# OPEN_DROP_DIGISCOPE_BOARD_1.net
KiCad netlist of a schematic drawn in EAGLE
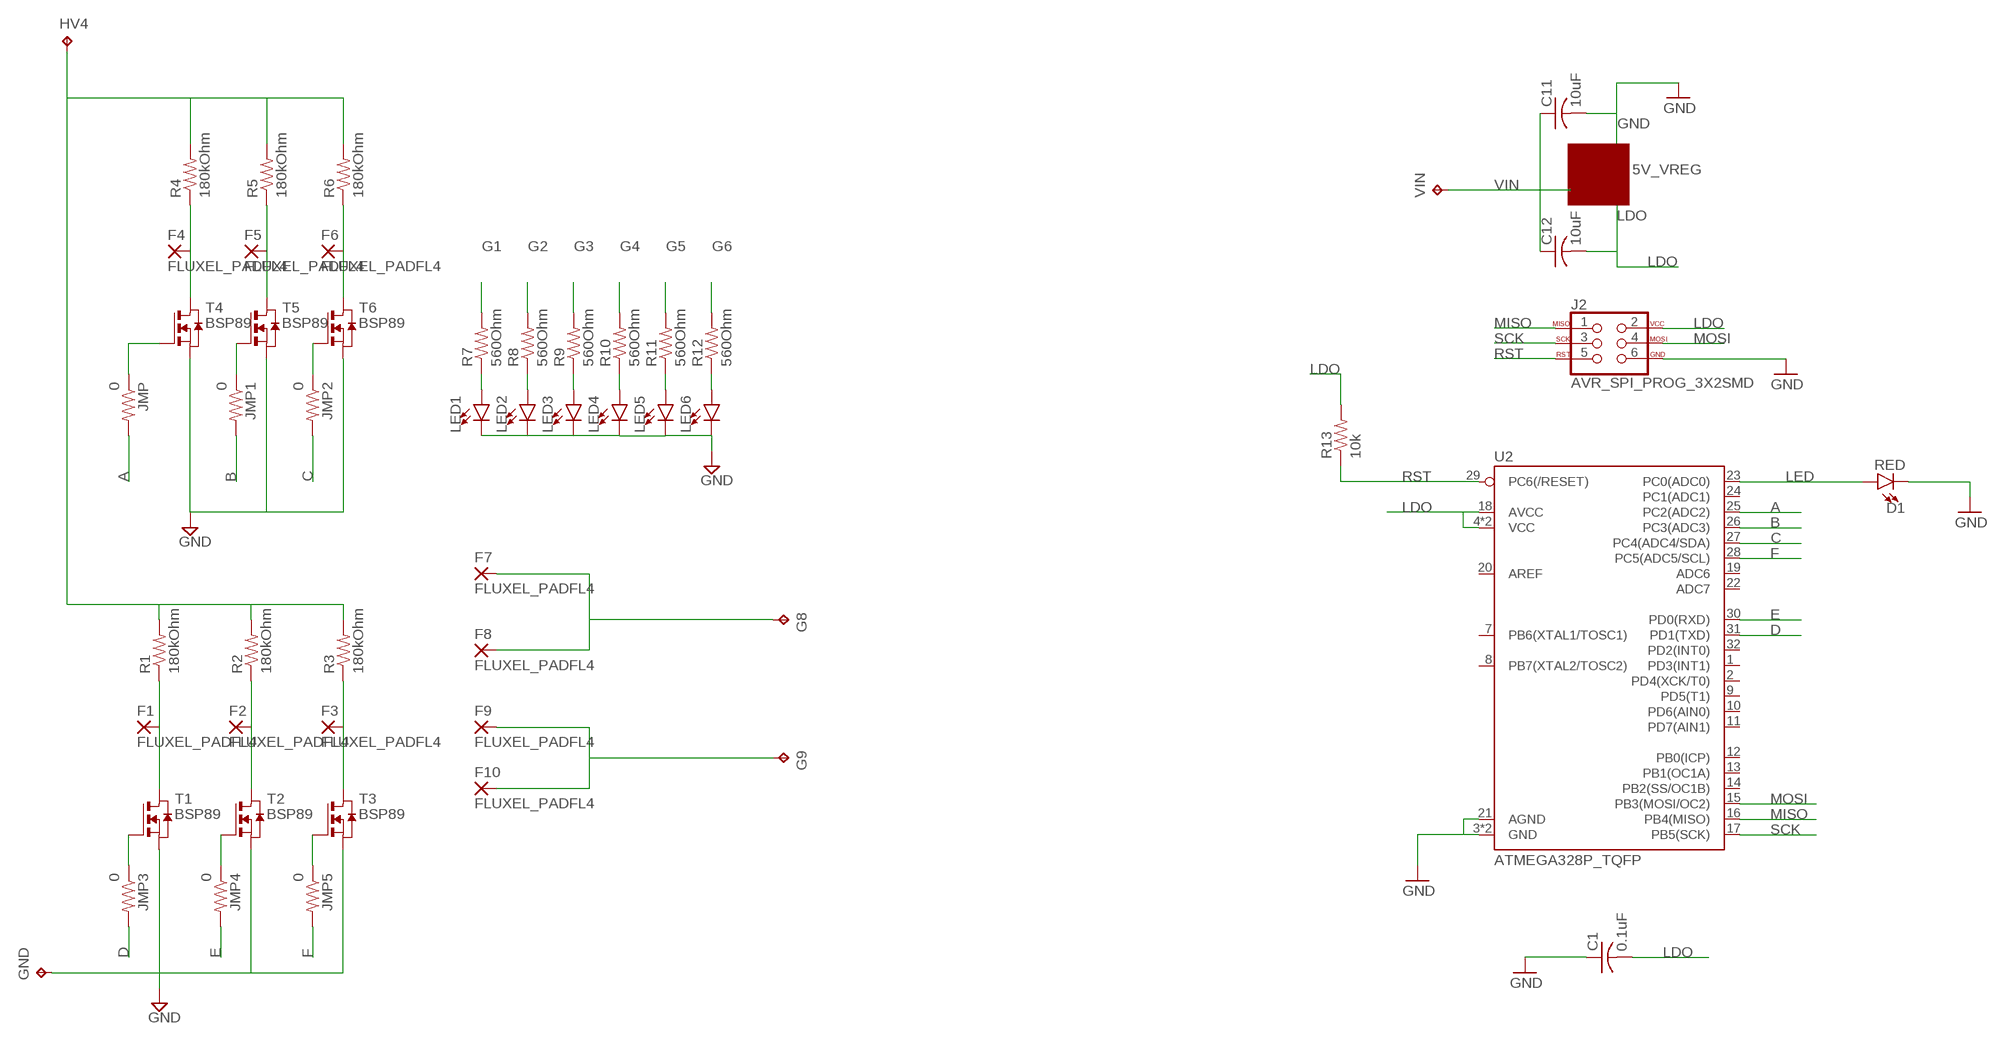
[diagram p0: schematic, sheet 1]

(export (version "E")
  (design (tool "Eeschema 10.0.6"))
  (components
    (comp (ref "5V_VREG")
      (value "MOSFET_PCH-DMG2305UX-7")
      (footprint "eagle-import:SOT23-3")
      (libsource (lib "eagle-import") (part "MOSFET_PCH-DMG2305UX-7"))
    )
    (comp (ref "C1")
      (value "0.1uF")
      (footprint "eagle-import:C1206")
      (libsource (lib "eagle-import") (part "C-USC1206"))
    )
    (comp (ref "C11")
      (value "10uF")
      (footprint "eagle-import:C1206")
      (libsource (lib "eagle-import") (part "C-USC1206"))
    )
    (comp (ref "C12")
      (value "10uF")
      (footprint "eagle-import:C1206")
      (libsource (lib "eagle-import") (part "C-USC1206"))
    )
    (comp (ref "D1")
      (value "RED")
      (footprint "eagle-import:LED-1206")
      (libsource (lib "eagle-import") (part "LED-RED1206"))
    )
    (comp (ref "F1")
      (value "FLUXEL_PADFL4")
      (footprint "eagle-import:FLUXEL_PAD4")
      (libsource (lib "eagle-import") (part "FLUXEL_PADFL4"))
    )
    (comp (ref "F2")
      (value "FLUXEL_PADFL4")
      (footprint "eagle-import:FLUXEL_PAD4")
      (libsource (lib "eagle-import") (part "FLUXEL_PADFL4"))
    )
    (comp (ref "F3")
      (value "FLUXEL_PADFL4")
      (footprint "eagle-import:FLUXEL_PAD4")
      (libsource (lib "eagle-import") (part "FLUXEL_PADFL4"))
    )
    (comp (ref "F4")
      (value "FLUXEL_PADFL4")
      (footprint "eagle-import:FLUXEL_PAD4")
      (libsource (lib "eagle-import") (part "FLUXEL_PADFL4"))
    )
    (comp (ref "F5")
      (value "FLUXEL_PADFL4")
      (footprint "eagle-import:FLUXEL_PAD4")
      (libsource (lib "eagle-import") (part "FLUXEL_PADFL4"))
    )
    (comp (ref "F6")
      (value "FLUXEL_PADFL4")
      (footprint "eagle-import:FLUXEL_PAD4")
      (libsource (lib "eagle-import") (part "FLUXEL_PADFL4"))
    )
    (comp (ref "F7")
      (value "FLUXEL_PADFL4")
      (footprint "eagle-import:FLUXEL_PAD4")
      (libsource (lib "eagle-import") (part "FLUXEL_PADFL4"))
    )
    (comp (ref "F8")
      (value "FLUXEL_PADFL4")
      (footprint "eagle-import:FLUXEL_PAD4")
      (libsource (lib "eagle-import") (part "FLUXEL_PADFL4"))
    )
    (comp (ref "F9")
      (value "FLUXEL_PADFL4")
      (footprint "eagle-import:FLUXEL_PAD4")
      (libsource (lib "eagle-import") (part "FLUXEL_PADFL4"))
    )
    (comp (ref "F10")
      (value "FLUXEL_PADFL4")
      (footprint "eagle-import:FLUXEL_PAD4")
      (libsource (lib "eagle-import") (part "FLUXEL_PADFL4"))
    )
    (comp (ref "G8")
      (value "TPB2,54")
      (footprint "eagle-import:B2,54")
      (libsource (lib "eagle-import") (part "TPB2,54"))
    )
    (comp (ref "G9")
      (value "TPB2,54")
      (footprint "eagle-import:B2,54")
      (libsource (lib "eagle-import") (part "TPB2,54"))
    )
    (comp (ref "GND")
      (value "TPB2,54")
      (footprint "eagle-import:B2,54")
      (libsource (lib "eagle-import") (part "TPB2,54"))
    )
    (comp (ref "HV4")
      (value "TPB2,54")
      (footprint "eagle-import:B2,54")
      (libsource (lib "eagle-import") (part "TPB2,54"))
    )
    (comp (ref "J2")
      (value "AVR_SPI_PROG_3X2SMD")
      (footprint "eagle-import:2X3_SMT_POSTS")
      (libsource (lib "eagle-import") (part "AVR_SPI_PROG_3X2SMD"))
    )
    (comp (ref "JMP")
      (value "0")
      (footprint "eagle-import:M1206")
      (libsource (lib "eagle-import") (part "R-US_M1206"))
    )
    (comp (ref "JMP1")
      (value "0")
      (footprint "eagle-import:M1206")
      (libsource (lib "eagle-import") (part "R-US_M1206"))
    )
    (comp (ref "JMP2")
      (value "0")
      (footprint "eagle-import:M1206")
      (libsource (lib "eagle-import") (part "R-US_M1206"))
    )
    (comp (ref "JMP3")
      (value "0")
      (footprint "eagle-import:M1206")
      (libsource (lib "eagle-import") (part "R-US_M1206"))
    )
    (comp (ref "JMP4")
      (value "0")
      (footprint "eagle-import:M1206")
      (libsource (lib "eagle-import") (part "R-US_M1206"))
    )
    (comp (ref "JMP5")
      (value "0")
      (footprint "eagle-import:M1206")
      (libsource (lib "eagle-import") (part "R-US_M1206"))
    )
    (comp (ref "LED1")
      (value "LED1206")
      (footprint "eagle-import:LED-1206")
      (libsource (lib "eagle-import") (part "LED1206"))
    )
    (comp (ref "LED2")
      (value "LED1206")
      (footprint "eagle-import:LED-1206")
      (libsource (lib "eagle-import") (part "LED1206"))
    )
    (comp (ref "LED3")
      (value "LED1206")
      (footprint "eagle-import:LED-1206")
      (libsource (lib "eagle-import") (part "LED1206"))
    )
    (comp (ref "LED4")
      (value "LED1206")
      (footprint "eagle-import:LED-1206")
      (libsource (lib "eagle-import") (part "LED1206"))
    )
    (comp (ref "LED5")
      (value "LED1206")
      (footprint "eagle-import:LED-1206")
      (libsource (lib "eagle-import") (part "LED1206"))
    )
    (comp (ref "LED6")
      (value "LED1206")
      (footprint "eagle-import:LED-1206")
      (libsource (lib "eagle-import") (part "LED1206"))
    )
    (comp (ref "R1")
      (value "180kOhm")
      (footprint "eagle-import:M1206")
      (libsource (lib "eagle-import") (part "R-US_M1206"))
    )
    (comp (ref "R2")
      (value "180kOhm")
      (footprint "eagle-import:M1206")
      (libsource (lib "eagle-import") (part "R-US_M1206"))
    )
    (comp (ref "R3")
      (value "180kOhm")
      (footprint "eagle-import:M1206")
      (libsource (lib "eagle-import") (part "R-US_M1206"))
    )
    (comp (ref "R4")
      (value "180kOhm")
      (footprint "eagle-import:M1206")
      (libsource (lib "eagle-import") (part "R-US_M1206"))
    )
    (comp (ref "R5")
      (value "180kOhm")
      (footprint "eagle-import:M1206")
      (libsource (lib "eagle-import") (part "R-US_M1206"))
    )
    (comp (ref "R6")
      (value "180kOhm")
      (footprint "eagle-import:M1206")
      (libsource (lib "eagle-import") (part "R-US_M1206"))
    )
    (comp (ref "R7")
      (value "560Ohm")
      (footprint "eagle-import:M1206")
      (libsource (lib "eagle-import") (part "R-US_M1206"))
    )
    (comp (ref "R8")
      (value "560Ohm")
      (footprint "eagle-import:M1206")
      (libsource (lib "eagle-import") (part "R-US_M1206"))
    )
    (comp (ref "R9")
      (value "560Ohm")
      (footprint "eagle-import:M1206")
      (libsource (lib "eagle-import") (part "R-US_M1206"))
    )
    (comp (ref "R10")
      (value "560Ohm")
      (footprint "eagle-import:M1206")
      (libsource (lib "eagle-import") (part "R-US_M1206"))
    )
    (comp (ref "R11")
      (value "560Ohm")
      (footprint "eagle-import:M1206")
      (libsource (lib "eagle-import") (part "R-US_M1206"))
    )
    (comp (ref "R12")
      (value "560Ohm")
      (footprint "eagle-import:M1206")
      (libsource (lib "eagle-import") (part "R-US_M1206"))
    )
    (comp (ref "R13")
      (value "10k")
      (footprint "eagle-import:R1206")
      (libsource (lib "eagle-import") (part "R-US_R1206"))
    )
    (comp (ref "T1")
      (value "BSP89")
      (footprint "eagle-import:SOT223")
      (libsource (lib "eagle-import") (part "NMOSSOT223"))
    )
    (comp (ref "T2")
      (value "BSP89")
      (footprint "eagle-import:SOT223")
      (libsource (lib "eagle-import") (part "NMOSSOT223"))
    )
    (comp (ref "T3")
      (value "BSP89")
      (footprint "eagle-import:SOT223")
      (libsource (lib "eagle-import") (part "NMOSSOT223"))
    )
    (comp (ref "T4")
      (value "BSP89")
      (footprint "eagle-import:SOT223")
      (libsource (lib "eagle-import") (part "NMOSSOT223"))
    )
    (comp (ref "T5")
      (value "BSP89")
      (footprint "eagle-import:SOT223")
      (libsource (lib "eagle-import") (part "NMOSSOT223"))
    )
    (comp (ref "T6")
      (value "BSP89")
      (footprint "eagle-import:SOT223")
      (libsource (lib "eagle-import") (part "NMOSSOT223"))
    )
    (comp (ref "U2")
      (value "ATMEGA328P_TQFP")
      (footprint "eagle-import:TQFP32-08")
      (libsource (lib "eagle-import") (part "ATMEGA328P_TQFP"))
    )
    (comp (ref "VIN")
      (value "TPB2,54")
      (footprint "eagle-import:B2,54")
      (libsource (lib "eagle-import") (part "TPB2,54"))
    )
  )
  (nets
    (net (code "1") (name "/A") (class "Default")
      (node (ref "JMP") (pin "2") (pinfunction "2_2") (pintype "passive"))
      (node (ref "U2") (pin "25") (pinfunction "PC2(ADC2)_25") (pintype "bidirectional"))
    )
    (net (code "2") (name "/B") (class "Default")
      (node (ref "JMP1") (pin "2") (pinfunction "2_2") (pintype "passive"))
      (node (ref "U2") (pin "26") (pinfunction "PC3(ADC3)_26") (pintype "bidirectional"))
    )
    (net (code "3") (name "/C") (class "Default")
      (node (ref "JMP2") (pin "2") (pinfunction "2_2") (pintype "passive"))
      (node (ref "U2") (pin "27") (pinfunction "PC4(ADC4/SDA)_27") (pintype "bidirectional"))
    )
    (net (code "4") (name "/D") (class "Default")
      (node (ref "JMP3") (pin "2") (pinfunction "2_2") (pintype "passive"))
      (node (ref "U2") (pin "31") (pinfunction "PD1(TXD)_31") (pintype "bidirectional"))
    )
    (net (code "5") (name "/E") (class "Default")
      (node (ref "JMP4") (pin "2") (pinfunction "2_2") (pintype "passive"))
      (node (ref "U2") (pin "30") (pinfunction "PD0(RXD)_30") (pintype "bidirectional"))
    )
    (net (code "6") (name "/F") (class "Default")
      (node (ref "JMP5") (pin "2") (pinfunction "2_2") (pintype "passive"))
      (node (ref "U2") (pin "28") (pinfunction "PC5(ADC5/SCL)_28") (pintype "bidirectional"))
    )
    (net (code "7") (name "/G1") (class "Default")
      (node (ref "JMP3") (pin "1") (pinfunction "1_1") (pintype "passive"))
      (node (ref "R7") (pin "2") (pinfunction "2_2") (pintype "passive"))
      (node (ref "T1") (pin "1") (pinfunction "G_1") (pintype "passive"))
    )
    (net (code "8") (name "/G2") (class "Default")
      (node (ref "JMP4") (pin "1") (pinfunction "1_1") (pintype "passive"))
      (node (ref "R8") (pin "2") (pinfunction "2_2") (pintype "passive"))
      (node (ref "T2") (pin "1") (pinfunction "G_1") (pintype "passive"))
    )
    (net (code "9") (name "/G3") (class "Default")
      (node (ref "JMP5") (pin "1") (pinfunction "1_1") (pintype "passive"))
      (node (ref "R9") (pin "2") (pinfunction "2_2") (pintype "passive"))
      (node (ref "T3") (pin "1") (pinfunction "G_1") (pintype "passive"))
    )
    (net (code "10") (name "/G4") (class "Default")
      (node (ref "JMP") (pin "1") (pinfunction "1_1") (pintype "passive"))
      (node (ref "R10") (pin "2") (pinfunction "2_2") (pintype "passive"))
      (node (ref "T4") (pin "1") (pinfunction "G_1") (pintype "passive"))
    )
    (net (code "11") (name "/G5") (class "Default")
      (node (ref "JMP1") (pin "1") (pinfunction "1_1") (pintype "passive"))
      (node (ref "R11") (pin "2") (pinfunction "2_2") (pintype "passive"))
      (node (ref "T5") (pin "1") (pinfunction "G_1") (pintype "passive"))
    )
    (net (code "12") (name "/G6") (class "Default")
      (node (ref "JMP2") (pin "1") (pinfunction "1_1") (pintype "passive"))
      (node (ref "R12") (pin "2") (pinfunction "2_2") (pintype "passive"))
      (node (ref "T6") (pin "1") (pinfunction "G_1") (pintype "passive"))
    )
    (net (code "13") (name "/LDO") (class "Default")
      (node (ref "5V_VREG") (pin "2") (pinfunction "S_2") (pintype "bidirectional"))
      (node (ref "C1") (pin "2") (pinfunction "2_2") (pintype "passive"))
      (node (ref "C12") (pin "2") (pinfunction "2_2") (pintype "passive"))
      (node (ref "J2") (pin "2") (pinfunction "2_2") (pintype "passive"))
      (node (ref "R13") (pin "2") (pinfunction "2_2") (pintype "passive"))
      (node (ref "U2") (pin "18") (pinfunction "AVCC_18") (pintype "bidirectional"))
      (node (ref "U2") (pin "4") (pinfunction "VCC_4") (pintype "bidirectional"))
      (node (ref "U2") (pin "6") (pinfunction "VCC_6") (pintype "bidirectional"))
    )
    (net (code "14") (name "/LED") (class "Default")
      (node (ref "D1") (pin "A") (pinfunction "A_A") (pintype "passive"))
      (node (ref "U2") (pin "23") (pinfunction "PC0(ADC0)_23") (pintype "bidirectional"))
    )
    (net (code "15") (name "/MISO") (class "Default")
      (node (ref "J2") (pin "1") (pinfunction "1_1") (pintype "passive"))
      (node (ref "U2") (pin "16") (pinfunction "PB4(MISO)_16") (pintype "bidirectional"))
    )
    (net (code "16") (name "/MOSI") (class "Default")
      (node (ref "J2") (pin "4") (pinfunction "4_4") (pintype "passive"))
      (node (ref "U2") (pin "15") (pinfunction "PB3(MOSI/OC2)_15") (pintype "bidirectional"))
    )
    (net (code "17") (name "/RST") (class "Default")
      (node (ref "J2") (pin "5") (pinfunction "5_5") (pintype "passive"))
      (node (ref "R13") (pin "1") (pinfunction "1_1") (pintype "passive"))
      (node (ref "U2") (pin "29") (pinfunction "PC6(/RESET)_29") (pintype "bidirectional"))
    )
    (net (code "18") (name "/SCK") (class "Default")
      (node (ref "J2") (pin "3") (pinfunction "3_3") (pintype "passive"))
      (node (ref "U2") (pin "17") (pinfunction "PB5(SCK)_17") (pintype "bidirectional"))
    )
    (net (code "19") (name "/VIN") (class "Default")
      (node (ref "5V_VREG") (pin "1") (pinfunction "G_1") (pintype "bidirectional"))
      (node (ref "C11") (pin "1") (pinfunction "1_1") (pintype "passive"))
      (node (ref "C12") (pin "1") (pinfunction "1_1") (pintype "passive"))
      (node (ref "VIN") (pin "TP") (pinfunction "TP_TP") (pintype "input"))
    )
    (net (code "20") (name "GND") (class "Default")
      (node (ref "5V_VREG") (pin "3") (pinfunction "D_3") (pintype "bidirectional"))
      (node (ref "C1") (pin "1") (pinfunction "1_1") (pintype "passive"))
      (node (ref "C11") (pin "2") (pinfunction "2_2") (pintype "passive"))
      (node (ref "D1") (pin "C") (pinfunction "C_C") (pintype "passive"))
      (node (ref "GND") (pin "TP") (pinfunction "TP_TP") (pintype "input"))
      (node (ref "J2") (pin "6") (pinfunction "6_6") (pintype "passive"))
      (node (ref "LED1") (pin "C") (pinfunction "C_C") (pintype "passive"))
      (node (ref "LED2") (pin "C") (pinfunction "C_C") (pintype "passive"))
      (node (ref "LED3") (pin "C") (pinfunction "C_C") (pintype "passive"))
      (node (ref "LED4") (pin "C") (pinfunction "C_C") (pintype "passive"))
      (node (ref "LED5") (pin "C") (pinfunction "C_C") (pintype "passive"))
      (node (ref "LED6") (pin "C") (pinfunction "C_C") (pintype "passive"))
      (node (ref "T1") (pin "3") (pinfunction "S_3") (pintype "passive"))
      (node (ref "T2") (pin "3") (pinfunction "S_3") (pintype "passive"))
      (node (ref "T3") (pin "3") (pinfunction "S_3") (pintype "passive"))
      (node (ref "T4") (pin "3") (pinfunction "S_3") (pintype "passive"))
      (node (ref "T5") (pin "3") (pinfunction "S_3") (pintype "passive"))
      (node (ref "T6") (pin "3") (pinfunction "S_3") (pintype "passive"))
      (node (ref "U2") (pin "21") (pinfunction "AGND_21") (pintype "bidirectional"))
      (node (ref "U2") (pin "3") (pinfunction "GND_3") (pintype "bidirectional"))
      (node (ref "U2") (pin "5") (pinfunction "GND_5") (pintype "bidirectional"))
    )
    (net (code "21") (name "Net-(F1-P)") (class "Default")
      (node (ref "F1") (pin "1") (pinfunction "P_1") (pintype "passive"))
      (node (ref "R1") (pin "1") (pinfunction "1_1") (pintype "passive"))
      (node (ref "T1") (pin "2") (pinfunction "D_2") (pintype "passive"))
      (node (ref "T1") (pin "4") (pinfunction "D_4") (pintype "passive"))
    )
    (net (code "22") (name "Net-(F2-P)") (class "Default")
      (node (ref "F2") (pin "1") (pinfunction "P_1") (pintype "passive"))
      (node (ref "R2") (pin "1") (pinfunction "1_1") (pintype "passive"))
      (node (ref "T2") (pin "2") (pinfunction "D_2") (pintype "passive"))
      (node (ref "T2") (pin "4") (pinfunction "D_4") (pintype "passive"))
    )
    (net (code "23") (name "Net-(F3-P)") (class "Default")
      (node (ref "F3") (pin "1") (pinfunction "P_1") (pintype "passive"))
      (node (ref "R3") (pin "1") (pinfunction "1_1") (pintype "passive"))
      (node (ref "T3") (pin "2") (pinfunction "D_2") (pintype "passive"))
      (node (ref "T3") (pin "4") (pinfunction "D_4") (pintype "passive"))
    )
    (net (code "24") (name "Net-(F4-P)") (class "Default")
      (node (ref "F4") (pin "1") (pinfunction "P_1") (pintype "passive"))
      (node (ref "R4") (pin "1") (pinfunction "1_1") (pintype "passive"))
      (node (ref "T4") (pin "2") (pinfunction "D_2") (pintype "passive"))
      (node (ref "T4") (pin "4") (pinfunction "D_4") (pintype "passive"))
    )
    (net (code "25") (name "Net-(F5-P)") (class "Default")
      (node (ref "F5") (pin "1") (pinfunction "P_1") (pintype "passive"))
      (node (ref "R5") (pin "1") (pinfunction "1_1") (pintype "passive"))
      (node (ref "T5") (pin "2") (pinfunction "D_2") (pintype "passive"))
      (node (ref "T5") (pin "4") (pinfunction "D_4") (pintype "passive"))
    )
    (net (code "26") (name "Net-(F6-P)") (class "Default")
      (node (ref "F6") (pin "1") (pinfunction "P_1") (pintype "passive"))
      (node (ref "R6") (pin "1") (pinfunction "1_1") (pintype "passive"))
      (node (ref "T6") (pin "2") (pinfunction "D_2") (pintype "passive"))
      (node (ref "T6") (pin "4") (pinfunction "D_4") (pintype "passive"))
    )
    (net (code "27") (name "Net-(F7-P)") (class "Default")
      (node (ref "F7") (pin "1") (pinfunction "P_1") (pintype "passive"))
      (node (ref "F8") (pin "1") (pinfunction "P_1") (pintype "passive"))
      (node (ref "G8") (pin "TP") (pinfunction "TP_TP") (pintype "input"))
    )
    (net (code "28") (name "Net-(F10-P)") (class "Default")
      (node (ref "F10") (pin "1") (pinfunction "P_1") (pintype "passive"))
      (node (ref "F9") (pin "1") (pinfunction "P_1") (pintype "passive"))
      (node (ref "G9") (pin "TP") (pinfunction "TP_TP") (pintype "input"))
    )
    (net (code "29") (name "Net-(HV4-PadTP)") (class "Default")
      (node (ref "HV4") (pin "TP") (pinfunction "TP_TP") (pintype "input"))
      (node (ref "R1") (pin "2") (pinfunction "2_2") (pintype "passive"))
      (node (ref "R2") (pin "2") (pinfunction "2_2") (pintype "passive"))
      (node (ref "R3") (pin "2") (pinfunction "2_2") (pintype "passive"))
      (node (ref "R4") (pin "2") (pinfunction "2_2") (pintype "passive"))
      (node (ref "R5") (pin "2") (pinfunction "2_2") (pintype "passive"))
      (node (ref "R6") (pin "2") (pinfunction "2_2") (pintype "passive"))
    )
    (net (code "30") (name "Net-(LED1-PadA)") (class "Default")
      (node (ref "LED1") (pin "A") (pinfunction "A_A") (pintype "passive"))
      (node (ref "R7") (pin "1") (pinfunction "1_1") (pintype "passive"))
    )
    (net (code "31") (name "Net-(LED2-PadA)") (class "Default")
      (node (ref "LED2") (pin "A") (pinfunction "A_A") (pintype "passive"))
      (node (ref "R8") (pin "1") (pinfunction "1_1") (pintype "passive"))
    )
    (net (code "32") (name "Net-(LED3-PadA)") (class "Default")
      (node (ref "LED3") (pin "A") (pinfunction "A_A") (pintype "passive"))
      (node (ref "R9") (pin "1") (pinfunction "1_1") (pintype "passive"))
    )
    (net (code "33") (name "Net-(LED4-PadA)") (class "Default")
      (node (ref "LED4") (pin "A") (pinfunction "A_A") (pintype "passive"))
      (node (ref "R10") (pin "1") (pinfunction "1_1") (pintype "passive"))
    )
    (net (code "34") (name "Net-(LED5-PadA)") (class "Default")
      (node (ref "LED5") (pin "A") (pinfunction "A_A") (pintype "passive"))
      (node (ref "R11") (pin "1") (pinfunction "1_1") (pintype "passive"))
    )
    (net (code "35") (name "Net-(LED6-PadA)") (class "Default")
      (node (ref "LED6") (pin "A") (pinfunction "A_A") (pintype "passive"))
      (node (ref "R12") (pin "1") (pinfunction "1_1") (pintype "passive"))
    )
    (net (code "36") (name "unconnected-(U2-ADC6-Pad19)") (class "Default")
      (node (ref "U2") (pin "19") (pinfunction "ADC6_19") (pintype "bidirectional"))
    )
    (net (code "37") (name "unconnected-(U2-ADC7-Pad22)") (class "Default")
      (node (ref "U2") (pin "22") (pinfunction "ADC7_22") (pintype "bidirectional"))
    )
    (net (code "38") (name "unconnected-(U2-AREF-Pad20)") (class "Default")
      (node (ref "U2") (pin "20") (pinfunction "AREF_20") (pintype "bidirectional"))
    )
    (net (code "39") (name "unconnected-(U2-PB0(ICP)-Pad12)") (class "Default")
      (node (ref "U2") (pin "12") (pinfunction "PB0(ICP)_12") (pintype "bidirectional"))
    )
    (net (code "40") (name "unconnected-(U2-PB1(OC1A)-Pad13)") (class "Default")
      (node (ref "U2") (pin "13") (pinfunction "PB1(OC1A)_13") (pintype "bidirectional"))
    )
    (net (code "41") (name "unconnected-(U2-PB2(SS{slash}OC1B)-Pad14)") (class "Default")
      (node (ref "U2") (pin "14") (pinfunction "PB2(SS/OC1B)_14") (pintype "bidirectional"))
    )
    (net (code "42") (name "unconnected-(U2-PB6(XTAL1{slash}TOSC1)-Pad7)") (class "Default")
      (node (ref "U2") (pin "7") (pinfunction "PB6(XTAL1/TOSC1)_7") (pintype "bidirectional"))
    )
    (net (code "43") (name "unconnected-(U2-PB7(XTAL2{slash}TOSC2)-Pad8)") (class "Default")
      (node (ref "U2") (pin "8") (pinfunction "PB7(XTAL2/TOSC2)_8") (pintype "bidirectional"))
    )
    (net (code "44") (name "unconnected-(U2-PC1(ADC1)-Pad24)") (class "Default")
      (node (ref "U2") (pin "24") (pinfunction "PC1(ADC1)_24") (pintype "bidirectional"))
    )
    (net (code "45") (name "unconnected-(U2-PD2(INT0)-Pad32)") (class "Default")
      (node (ref "U2") (pin "32") (pinfunction "PD2(INT0)_32") (pintype "bidirectional"))
    )
    (net (code "46") (name "unconnected-(U2-PD3(INT1)-Pad1)") (class "Default")
      (node (ref "U2") (pin "1") (pinfunction "PD3(INT1)_1") (pintype "bidirectional"))
    )
    (net (code "47") (name "unconnected-(U2-PD4(XCK{slash}T0)-Pad2)") (class "Default")
      (node (ref "U2") (pin "2") (pinfunction "PD4(XCK/T0)_2") (pintype "bidirectional"))
    )
    (net (code "48") (name "unconnected-(U2-PD5(T1)-Pad9)") (class "Default")
      (node (ref "U2") (pin "9") (pinfunction "PD5(T1)_9") (pintype "bidirectional"))
    )
    (net (code "49") (name "unconnected-(U2-PD6(AIN0)-Pad10)") (class "Default")
      (node (ref "U2") (pin "10") (pinfunction "PD6(AIN0)_10") (pintype "bidirectional"))
    )
    (net (code "50") (name "unconnected-(U2-PD7(AIN1)-Pad11)") (class "Default")
      (node (ref "U2") (pin "11") (pinfunction "PD7(AIN1)_11") (pintype "bidirectional"))
    )
  )
)
